# apu_mega_shield.net
KiCad netlist of a schematic drawn in EAGLE
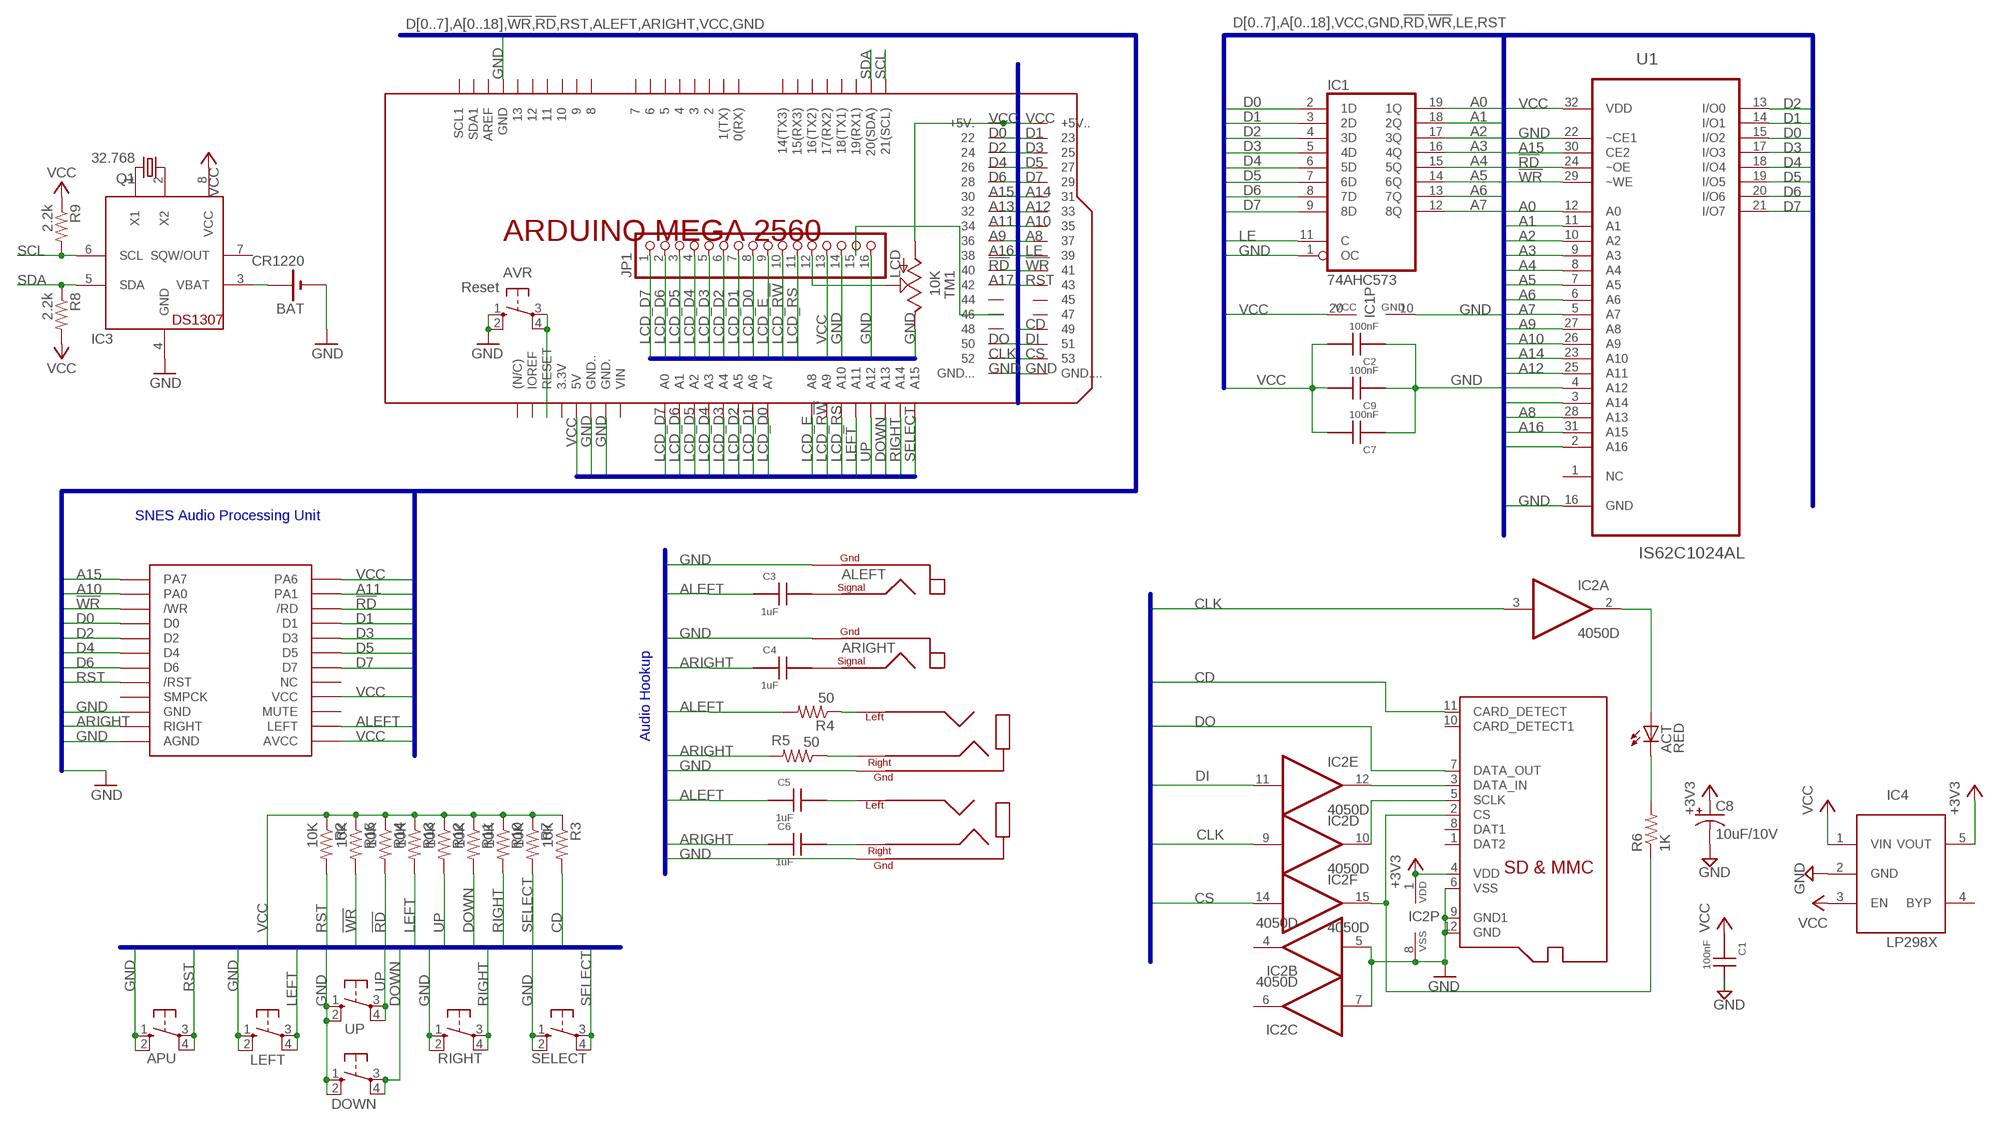
[diagram p0: schematic, sheet 1]

(export (version "E")
  (design (tool "Eeschema 10.0.6"))
  (components
    (comp (ref "ACT")
      (value "RED")
      (footprint "eagle-import:CHIP-LED0805")
      (libsource (lib "eagle-import") (part "LEDCHIP-LED0805"))
    )
    (comp (ref "APU")
      (value "Reset")
      (footprint "eagle-import:B3F-10XX")
      (libsource (lib "eagle-import") (part "10-XX"))
    )
    (comp (ref "AVR")
      (value "Reset")
      (footprint "eagle-import:B3F-10XX")
      (libsource (lib "eagle-import") (part "10-XX"))
    )
    (comp (ref "BAT")
      (value "CR1220")
      (footprint "eagle-import:CR1220-SMD")
      (libsource (lib "eagle-import") (part "CR1220SMT"))
    )
    (comp (ref "C1")
      (value "100nF")
      (footprint "eagle-import:C0805")
      (libsource (lib "eagle-import") (part "C0805"))
    )
    (comp (ref "C2")
      (value "100nF")
      (footprint "eagle-import:C0805")
      (libsource (lib "eagle-import") (part "C0805"))
    )
    (comp (ref "C3")
      (value "1uF")
      (footprint "eagle-import:C0805")
      (libsource (lib "eagle-import") (part "C0805"))
    )
    (comp (ref "C4")
      (value "1uF")
      (footprint "eagle-import:C0805")
      (libsource (lib "eagle-import") (part "C0805"))
    )
    (comp (ref "C5")
      (value "1uF")
      (footprint "eagle-import:C0805")
      (libsource (lib "eagle-import") (part "C0805"))
    )
    (comp (ref "C6")
      (value "1uF")
      (footprint "eagle-import:C0805")
      (libsource (lib "eagle-import") (part "C0805"))
    )
    (comp (ref "C7")
      (value "100nF")
      (footprint "eagle-import:C0805")
      (libsource (lib "eagle-import") (part "C0805"))
    )
    (comp (ref "C8")
      (value "10uF/10V")
      (footprint "eagle-import:A_3216-18R")
      (libsource (lib "eagle-import") (part "CPOL-USA/3216-18R"))
    )
    (comp (ref "C9")
      (value "100nF")
      (footprint "eagle-import:C0805")
      (libsource (lib "eagle-import") (part "C0805"))
    )
    (comp (ref "DOWN")
      (value "10-XX")
      (footprint "eagle-import:B3F-10XX")
      (libsource (lib "eagle-import") (part "10-XX"))
    )
    (comp (ref "IC1")
      (value "74AHC573")
      (footprint "eagle-import:SO20W")
      (libsource (lib "eagle-import") (part "74573DHCT"))
    )
    (comp (ref "IC2")
      (value "4050D")
      (footprint "eagle-import:SO16")
      (libsource (lib "eagle-import") (part "4050D"))
    )
    (comp (ref "IC3")
      (value "DS1307")
      (footprint "eagle-import:SO-08")
      (libsource (lib "eagle-import") (part "DS1307SMT"))
    )
    (comp (ref "IC4")
      (value "LP298XS")
      (footprint "eagle-import:SOT23-5L")
      (libsource (lib "eagle-import") (part "LP298XS"))
    )
    (comp (ref "JP1")
      (value "LCD")
      (footprint "eagle-import:1X16")
      (libsource (lib "eagle-import") (part "PINHD-1X16"))
    )
    (comp (ref "LEFT")
      (value "10-XX")
      (footprint "eagle-import:B3F-10XX")
      (libsource (lib "eagle-import") (part "10-XX"))
    )
    (comp (ref "Q1")
      (value "32.768")
      (footprint "eagle-import:SMD")
      (libsource (lib "eagle-import") (part "CRYTALSMD"))
    )
    (comp (ref "R2")
      (value "10K")
      (footprint "eagle-import:R0805")
      (libsource (lib "eagle-import") (part "R-US_R0805"))
    )
    (comp (ref "R3")
      (value "10K")
      (footprint "eagle-import:R0805")
      (libsource (lib "eagle-import") (part "R-US_R0805"))
    )
    (comp (ref "R4")
      (value "50")
      (footprint "eagle-import:R0805")
      (libsource (lib "eagle-import") (part "R-US_R0805"))
    )
    (comp (ref "R5")
      (value "50")
      (footprint "eagle-import:R0805")
      (libsource (lib "eagle-import") (part "R-US_R0805"))
    )
    (comp (ref "R6")
      (value "1K")
      (footprint "eagle-import:R0805")
      (libsource (lib "eagle-import") (part "R-US_R0805"))
    )
    (comp (ref "R7")
      (value "10K")
      (footprint "eagle-import:R0805")
      (libsource (lib "eagle-import") (part "R-US_R0805"))
    )
    (comp (ref "R8")
      (value "2.2k")
      (footprint "eagle-import:R0805")
      (libsource (lib "eagle-import") (part "R-US_R0805"))
    )
    (comp (ref "R9")
      (value "2.2k")
      (footprint "eagle-import:R0805")
      (libsource (lib "eagle-import") (part "R-US_R0805"))
    )
    (comp (ref "R10")
      (value "10K")
      (footprint "eagle-import:R0805")
      (libsource (lib "eagle-import") (part "R-US_R0805"))
    )
    (comp (ref "R11")
      (value "10K")
      (footprint "eagle-import:R0805")
      (libsource (lib "eagle-import") (part "R-US_R0805"))
    )
    (comp (ref "R12")
      (value "10K")
      (footprint "eagle-import:R0805")
      (libsource (lib "eagle-import") (part "R-US_R0805"))
    )
    (comp (ref "R13")
      (value "10K")
      (footprint "eagle-import:R0805")
      (libsource (lib "eagle-import") (part "R-US_R0805"))
    )
    (comp (ref "R14")
      (value "10K")
      (footprint "eagle-import:R0805")
      (libsource (lib "eagle-import") (part "R-US_R0805"))
    )
    (comp (ref "R15")
      (value "10K")
      (footprint "eagle-import:R0805")
      (libsource (lib "eagle-import") (part "R-US_R0805"))
    )
    (comp (ref "RIGHT")
      (value "10-XX")
      (footprint "eagle-import:B3F-10XX")
      (libsource (lib "eagle-import") (part "10-XX"))
    )
    (comp (ref "SELECT")
      (value "10-XX")
      (footprint "eagle-import:B3F-10XX")
      (libsource (lib "eagle-import") (part "10-XX"))
    )
    (comp (ref "TM1")
      (value "10K")
      (footprint "eagle-import:CA6H")
      (libsource (lib "eagle-import") (part "TRIM_US-CA6H"))
    )
    (comp (ref "U$1")
      (value "APU")
      (footprint "eagle-import:APU")
      (libsource (lib "eagle-import") (part "APU"))
    )
    (comp (ref "U$2")
      (value "HEADPHONE")
      (footprint "eagle-import:SJ1-3533N")
      (libsource (lib "eagle-import") (part "HEADPHONE"))
    )
    (comp (ref "U$3")
      (value "HEADPHONE")
      (footprint "eagle-import:SJ1-3533N")
      (libsource (lib "eagle-import") (part "HEADPHONE"))
    )
    (comp (ref "U$4")
      (value "RCA")
      (footprint "eagle-import:RCJ-01X")
      (libsource (lib "eagle-import") (part "RCA"))
    )
    (comp (ref "U$5")
      (value "RCA")
      (footprint "eagle-import:RCJ-01X")
      (libsource (lib "eagle-import") (part "RCA"))
    )
    (comp (ref "U$6")
      (value "ARDUINO_MEGA_2560_LITENO_LABELS")
      (footprint "eagle-import:ARDUINO_MEGA2560_LITE_NO_LABELS")
      (libsource (lib "eagle-import") (part "ARDUINO_MEGA_2560_LITENO_LABELS"))
    )
    (comp (ref "U1")
      (value "IS62C1024AL")
      (footprint "eagle-import:SOIC127P1412X305-32N")
      (fields (field (name "MPN") "IS62C1024AL-35QLI"))
      (libsource (lib "eagle-import") (part "IS62C1024AL-35QLI"))
    )
    (comp (ref "UP")
      (value "10-XX")
      (footprint "eagle-import:B3F-10XX")
      (libsource (lib "eagle-import") (part "10-XX"))
    )
    (comp (ref "X1")
      (value "MICROSDMOLEX")
      (footprint "eagle-import:MICROSD-1")
      (libsource (lib "eagle-import") (part "MICROSDMOLEX"))
    )
  )
  (nets
    (net (code "1") (name "+3V3") (class "Default")
      (node (ref "C8") (pin "+") (pinfunction "+_+") (pintype "passive"))
      (node (ref "IC2") (pin "1") (pinfunction "VDD_1") (pintype "power_in"))
      (node (ref "IC4") (pin "5") (pinfunction "VOUT_5") (pintype "bidirectional"))
      (node (ref "X1") (pin "4") (pinfunction "VDD_4") (pintype "power_in"))
    )
    (net (code "2") (name "/A0") (class "Default")
      (node (ref "IC1") (pin "19") (pinfunction "1Q_19") (pintype "tri_state"))
      (node (ref "U1") (pin "12") (pinfunction "A0_12") (pintype "input"))
    )
    (net (code "3") (name "/A1") (class "Default")
      (node (ref "IC1") (pin "18") (pinfunction "2Q_18") (pintype "tri_state"))
      (node (ref "U1") (pin "11") (pinfunction "A1_11") (pintype "input"))
    )
    (net (code "4") (name "/A2") (class "Default")
      (node (ref "IC1") (pin "17") (pinfunction "3Q_17") (pintype "tri_state"))
      (node (ref "U1") (pin "10") (pinfunction "A2_10") (pintype "input"))
    )
    (net (code "5") (name "/A3") (class "Default")
      (node (ref "IC1") (pin "16") (pinfunction "4Q_16") (pintype "tri_state"))
      (node (ref "U1") (pin "9") (pinfunction "A3_9") (pintype "input"))
    )
    (net (code "6") (name "/A4") (class "Default")
      (node (ref "IC1") (pin "15") (pinfunction "5Q_15") (pintype "tri_state"))
      (node (ref "U1") (pin "8") (pinfunction "A4_8") (pintype "input"))
    )
    (net (code "7") (name "/A5") (class "Default")
      (node (ref "IC1") (pin "14") (pinfunction "6Q_14") (pintype "tri_state"))
      (node (ref "U1") (pin "7") (pinfunction "A5_7") (pintype "input"))
    )
    (net (code "8") (name "/A6") (class "Default")
      (node (ref "IC1") (pin "13") (pinfunction "7Q_13") (pintype "tri_state"))
      (node (ref "U1") (pin "6") (pinfunction "A6_6") (pintype "input"))
    )
    (net (code "9") (name "/A7") (class "Default")
      (node (ref "IC1") (pin "12") (pinfunction "8Q_12") (pintype "tri_state"))
      (node (ref "U1") (pin "5") (pinfunction "A7_5") (pintype "input"))
    )
    (net (code "10") (name "/A8") (class "Default")
      (node (ref "U$6") (pin "37") (pinfunction "37_37") (pintype "bidirectional"))
      (node (ref "U1") (pin "28") (pinfunction "A13_28") (pintype "input"))
    )
    (net (code "11") (name "/A9") (class "Default")
      (node (ref "U$6") (pin "36") (pinfunction "36_36") (pintype "bidirectional"))
      (node (ref "U1") (pin "27") (pinfunction "A8_27") (pintype "input"))
    )
    (net (code "12") (name "/A10") (class "Default")
      (node (ref "U$1") (pin "P$3") (pinfunction "PA0_P$3") (pintype "bidirectional"))
      (node (ref "U$6") (pin "35") (pinfunction "35_35") (pintype "bidirectional"))
      (node (ref "U1") (pin "26") (pinfunction "A9_26") (pintype "input"))
    )
    (net (code "13") (name "/A11") (class "Default")
      (node (ref "U$1") (pin "P$4") (pinfunction "PA1_P$4") (pintype "bidirectional"))
      (node (ref "U$6") (pin "34") (pinfunction "34_34") (pintype "bidirectional"))
      (node (ref "U1") (pin "3") (pinfunction "A14_3") (pintype "input"))
    )
    (net (code "14") (name "/A12") (class "Default")
      (node (ref "U$6") (pin "33") (pinfunction "33_33") (pintype "bidirectional"))
      (node (ref "U1") (pin "25") (pinfunction "A11_25") (pintype "input"))
    )
    (net (code "15") (name "/A13") (class "Default")
      (node (ref "U$6") (pin "32") (pinfunction "32_32") (pintype "bidirectional"))
      (node (ref "U1") (pin "4") (pinfunction "A12_4") (pintype "input"))
    )
    (net (code "16") (name "/A14") (class "Default")
      (node (ref "U$6") (pin "31") (pinfunction "31_31") (pintype "bidirectional"))
      (node (ref "U1") (pin "23") (pinfunction "A10_23") (pintype "input"))
    )
    (net (code "17") (name "/A15") (class "Default")
      (node (ref "U$1") (pin "P$1") (pinfunction "PA7_P$1") (pintype "bidirectional"))
      (node (ref "U$6") (pin "30") (pinfunction "30_30") (pintype "bidirectional"))
      (node (ref "U1") (pin "30") (pinfunction "CE2_30") (pintype "input"))
    )
    (net (code "18") (name "/A16") (class "Default")
      (node (ref "U$6") (pin "38") (pinfunction "38_38") (pintype "bidirectional"))
      (node (ref "U1") (pin "31") (pinfunction "A15_31") (pintype "input"))
    )
    (net (code "19") (name "/A17") (class "Default")
      (node (ref "U$6") (pin "42") (pinfunction "42_42") (pintype "bidirectional"))
      (node (ref "U1") (pin "2") (pinfunction "A16_2") (pintype "input"))
    )
    (net (code "20") (name "/ALEFT") (class "Default")
      (node (ref "C3") (pin "1") (pinfunction "1_1") (pintype "bidirectional"))
      (node (ref "C5") (pin "1") (pinfunction "1_1") (pintype "bidirectional"))
      (node (ref "R4") (pin "2") (pinfunction "2_2") (pintype "passive"))
      (node (ref "U$1") (pin "P$22") (pinfunction "LEFT_P$22") (pintype "bidirectional"))
    )
    (net (code "21") (name "/ARIGHT") (class "Default")
      (node (ref "C4") (pin "1") (pinfunction "1_1") (pintype "bidirectional"))
      (node (ref "C6") (pin "1") (pinfunction "1_1") (pintype "bidirectional"))
      (node (ref "R5") (pin "2") (pinfunction "2_2") (pintype "passive"))
      (node (ref "U$1") (pin "P$21") (pinfunction "RIGHT_P$21") (pintype "bidirectional"))
    )
    (net (code "22") (name "/CD") (class "Default")
      (node (ref "R3") (pin "2") (pinfunction "2_2") (pintype "passive"))
      (node (ref "U$6") (pin "49") (pinfunction "49_49") (pintype "bidirectional"))
      (node (ref "X1") (pin "11") (pinfunction "CARD_DETECT_11") (pintype "passive"))
    )
    (net (code "23") (name "/CLK") (class "Default")
      (node (ref "IC2") (pin "3") (pinfunction "I_3") (pintype "input"))
      (node (ref "IC2") (pin "9") (pinfunction "I_9") (pintype "input"))
      (node (ref "U$6") (pin "52") (pinfunction "52_52") (pintype "bidirectional"))
    )
    (net (code "24") (name "/CS") (class "Default")
      (node (ref "IC2") (pin "14") (pinfunction "I_14") (pintype "input"))
      (node (ref "U$6") (pin "53") (pinfunction "53_53") (pintype "bidirectional"))
    )
    (net (code "25") (name "/D0") (class "Default")
      (node (ref "IC1") (pin "2") (pinfunction "1D_2") (pintype "input"))
      (node (ref "U$1") (pin "P$7") (pinfunction "D0_P$7") (pintype "bidirectional"))
      (node (ref "U$6") (pin "22") (pinfunction "22_22") (pintype "bidirectional"))
      (node (ref "U1") (pin "15") (pinfunction "I/O2_15") (pintype "bidirectional"))
    )
    (net (code "26") (name "/D1") (class "Default")
      (node (ref "IC1") (pin "3") (pinfunction "2D_3") (pintype "input"))
      (node (ref "U$1") (pin "P$8") (pinfunction "D1_P$8") (pintype "bidirectional"))
      (node (ref "U$6") (pin "23") (pinfunction "23_23") (pintype "bidirectional"))
      (node (ref "U1") (pin "14") (pinfunction "I/O1_14") (pintype "bidirectional"))
    )
    (net (code "27") (name "/D2") (class "Default")
      (node (ref "IC1") (pin "4") (pinfunction "3D_4") (pintype "input"))
      (node (ref "U$1") (pin "P$9") (pinfunction "D2_P$9") (pintype "bidirectional"))
      (node (ref "U$6") (pin "24") (pinfunction "24_24") (pintype "bidirectional"))
      (node (ref "U1") (pin "13") (pinfunction "I/O0_13") (pintype "bidirectional"))
    )
    (net (code "28") (name "/D3") (class "Default")
      (node (ref "IC1") (pin "5") (pinfunction "4D_5") (pintype "input"))
      (node (ref "U$1") (pin "P$10") (pinfunction "D3_P$10") (pintype "bidirectional"))
      (node (ref "U$6") (pin "25") (pinfunction "25_25") (pintype "bidirectional"))
      (node (ref "U1") (pin "17") (pinfunction "I/O3_17") (pintype "bidirectional"))
    )
    (net (code "29") (name "/D4") (class "Default")
      (node (ref "IC1") (pin "6") (pinfunction "5D_6") (pintype "input"))
      (node (ref "U$1") (pin "P$11") (pinfunction "D4_P$11") (pintype "bidirectional"))
      (node (ref "U$6") (pin "26") (pinfunction "26_26") (pintype "bidirectional"))
      (node (ref "U1") (pin "18") (pinfunction "I/O4_18") (pintype "bidirectional"))
    )
    (net (code "30") (name "/D5") (class "Default")
      (node (ref "IC1") (pin "7") (pinfunction "6D_7") (pintype "input"))
      (node (ref "U$1") (pin "P$12") (pinfunction "D5_P$12") (pintype "bidirectional"))
      (node (ref "U$6") (pin "27") (pinfunction "27_27") (pintype "bidirectional"))
      (node (ref "U1") (pin "19") (pinfunction "I/O5_19") (pintype "bidirectional"))
    )
    (net (code "31") (name "/D6") (class "Default")
      (node (ref "IC1") (pin "8") (pinfunction "7D_8") (pintype "input"))
      (node (ref "U$1") (pin "P$13") (pinfunction "D6_P$13") (pintype "bidirectional"))
      (node (ref "U$6") (pin "28") (pinfunction "28_28") (pintype "bidirectional"))
      (node (ref "U1") (pin "20") (pinfunction "I/O6_20") (pintype "bidirectional"))
    )
    (net (code "32") (name "/D7") (class "Default")
      (node (ref "IC1") (pin "9") (pinfunction "8D_9") (pintype "input"))
      (node (ref "U$1") (pin "P$14") (pinfunction "D7_P$14") (pintype "bidirectional"))
      (node (ref "U$6") (pin "29") (pinfunction "29_29") (pintype "bidirectional"))
      (node (ref "U1") (pin "21") (pinfunction "I/O7_21") (pintype "bidirectional"))
    )
    (net (code "33") (name "/DI") (class "Default")
      (node (ref "IC2") (pin "11") (pinfunction "I_11") (pintype "input"))
      (node (ref "U$6") (pin "51") (pinfunction "51_51") (pintype "bidirectional"))
    )
    (net (code "34") (name "/DO") (class "Default")
      (node (ref "U$6") (pin "50") (pinfunction "50_50") (pintype "bidirectional"))
      (node (ref "X1") (pin "7") (pinfunction "DATA_OUT_7") (pintype "output"))
    )
    (net (code "35") (name "/DOWN") (class "Default")
      (node (ref "DOWN") (pin "3") (pinfunction "P_3") (pintype "passive"))
      (node (ref "DOWN") (pin "4") (pinfunction "P1_4") (pintype "passive"))
      (node (ref "R11") (pin "2") (pinfunction "2_2") (pintype "passive"))
      (node (ref "U$6") (pin "A13") (pinfunction "A13_A13") (pintype "bidirectional"))
    )
    (net (code "36") (name "/LCD_D0") (class "Default")
      (node (ref "JP1") (pin "8") (pinfunction "8_8") (pintype "passive"))
      (node (ref "U$6") (pin "A7") (pinfunction "A7_A7") (pintype "bidirectional"))
    )
    (net (code "37") (name "/LCD_D1") (class "Default")
      (node (ref "JP1") (pin "7") (pinfunction "7_7") (pintype "passive"))
      (node (ref "U$6") (pin "A6") (pinfunction "A6_A6") (pintype "bidirectional"))
    )
    (net (code "38") (name "/LCD_D2") (class "Default")
      (node (ref "JP1") (pin "6") (pinfunction "6_6") (pintype "passive"))
      (node (ref "U$6") (pin "A5") (pinfunction "A5_A5") (pintype "bidirectional"))
    )
    (net (code "39") (name "/LCD_D3") (class "Default")
      (node (ref "JP1") (pin "5") (pinfunction "5_5") (pintype "passive"))
      (node (ref "U$6") (pin "A4") (pinfunction "A4_A4") (pintype "bidirectional"))
    )
    (net (code "40") (name "/LCD_D4") (class "Default")
      (node (ref "JP1") (pin "4") (pinfunction "4_4") (pintype "passive"))
      (node (ref "U$6") (pin "A3") (pinfunction "A3_A3") (pintype "bidirectional"))
    )
    (net (code "41") (name "/LCD_D5") (class "Default")
      (node (ref "JP1") (pin "3") (pinfunction "3_3") (pintype "passive"))
      (node (ref "U$6") (pin "A2") (pinfunction "A2_A2") (pintype "bidirectional"))
    )
    (net (code "42") (name "/LCD_D6") (class "Default")
      (node (ref "JP1") (pin "2") (pinfunction "2_2") (pintype "passive"))
      (node (ref "U$6") (pin "A1") (pinfunction "A1_A1") (pintype "bidirectional"))
    )
    (net (code "43") (name "/LCD_D7") (class "Default")
      (node (ref "JP1") (pin "1") (pinfunction "1_1") (pintype "passive"))
      (node (ref "U$6") (pin "A0") (pinfunction "A0_A0") (pintype "bidirectional"))
    )
    (net (code "44") (name "/LCD_E") (class "Default")
      (node (ref "JP1") (pin "9") (pinfunction "9_9") (pintype "passive"))
      (node (ref "U$6") (pin "A8") (pinfunction "A8_A8") (pintype "bidirectional"))
    )
    (net (code "45") (name "/LCD_RS") (class "Default")
      (node (ref "JP1") (pin "11") (pinfunction "11_11") (pintype "passive"))
      (node (ref "U$6") (pin "A10") (pinfunction "A10_A10") (pintype "bidirectional"))
    )
    (net (code "46") (name "/LCD_R~{W}") (class "Default")
      (node (ref "JP1") (pin "10") (pinfunction "10_10") (pintype "passive"))
      (node (ref "U$6") (pin "A9") (pinfunction "A9_A9") (pintype "bidirectional"))
    )
    (net (code "47") (name "/LE") (class "Default")
      (node (ref "IC1") (pin "11") (pinfunction "C_11") (pintype "input"))
      (node (ref "U$6") (pin "39") (pinfunction "39_39") (pintype "bidirectional"))
    )
    (net (code "48") (name "/LEFT") (class "Default")
      (node (ref "LEFT") (pin "3") (pinfunction "P_3") (pintype "passive"))
      (node (ref "LEFT") (pin "4") (pinfunction "P1_4") (pintype "passive"))
      (node (ref "R13") (pin "2") (pinfunction "2_2") (pintype "passive"))
      (node (ref "U$6") (pin "A11") (pinfunction "A11_A11") (pintype "bidirectional"))
    )
    (net (code "49") (name "/RIGHT") (class "Default")
      (node (ref "R10") (pin "2") (pinfunction "2_2") (pintype "passive"))
      (node (ref "RIGHT") (pin "3") (pinfunction "P_3") (pintype "passive"))
      (node (ref "RIGHT") (pin "4") (pinfunction "P1_4") (pintype "passive"))
      (node (ref "U$6") (pin "A14") (pinfunction "A14_A14") (pintype "bidirectional"))
    )
    (net (code "50") (name "/RST") (class "Default")
      (node (ref "APU") (pin "3") (pinfunction "P_3") (pintype "passive"))
      (node (ref "APU") (pin "4") (pinfunction "P1_4") (pintype "passive"))
      (node (ref "R2") (pin "2") (pinfunction "2_2") (pintype "passive"))
      (node (ref "U$1") (pin "P$15") (pinfunction "/RST_P$15") (pintype "bidirectional"))
      (node (ref "U$6") (pin "43") (pinfunction "43_43") (pintype "bidirectional"))
    )
    (net (code "51") (name "/SCL") (class "Default")
      (node (ref "IC3") (pin "6") (pinfunction "SCL_6") (pintype "bidirectional"))
      (node (ref "R9") (pin "2") (pinfunction "2_2") (pintype "passive"))
      (node (ref "U$6") (pin "21") (pinfunction "21(SCL)_21") (pintype "bidirectional"))
    )
    (net (code "52") (name "/SDA") (class "Default")
      (node (ref "IC3") (pin "5") (pinfunction "SDA_5") (pintype "bidirectional"))
      (node (ref "R8") (pin "1") (pinfunction "1_1") (pintype "passive"))
      (node (ref "U$6") (pin "20") (pinfunction "20(SDA)_20") (pintype "bidirectional"))
    )
    (net (code "53") (name "/SELECT") (class "Default")
      (node (ref "R7") (pin "2") (pinfunction "2_2") (pintype "passive"))
      (node (ref "SELECT") (pin "3") (pinfunction "P_3") (pintype "passive"))
      (node (ref "SELECT") (pin "4") (pinfunction "P1_4") (pintype "passive"))
      (node (ref "U$6") (pin "A15") (pinfunction "A15_A15") (pintype "bidirectional"))
    )
    (net (code "54") (name "/UP") (class "Default")
      (node (ref "R12") (pin "2") (pinfunction "2_2") (pintype "passive"))
      (node (ref "U$6") (pin "A12") (pinfunction "A12_A12") (pintype "bidirectional"))
      (node (ref "UP") (pin "3") (pinfunction "P_3") (pintype "passive"))
      (node (ref "UP") (pin "4") (pinfunction "P1_4") (pintype "passive"))
    )
    (net (code "57") (name "/~{RD}") (class "Default")
      (node (ref "R14") (pin "2") (pinfunction "2_2") (pintype "passive"))
      (node (ref "U$1") (pin "P$6") (pinfunction "/RD_P$6") (pintype "bidirectional"))
      (node (ref "U$6") (pin "40") (pinfunction "40_40") (pintype "bidirectional"))
      (node (ref "U1") (pin "24") (pinfunction "~{OE}_24") (pintype "input"))
    )
    (net (code "58") (name "/~{WR}") (class "Default")
      (node (ref "R15") (pin "2") (pinfunction "2_2") (pintype "passive"))
      (node (ref "U$1") (pin "P$5") (pinfunction "/WR_P$5") (pintype "bidirectional"))
      (node (ref "U$6") (pin "41") (pinfunction "41_41") (pintype "bidirectional"))
      (node (ref "U1") (pin "29") (pinfunction "~{WE}_29") (pintype "input"))
    )
    (net (code "59") (name "GND") (class "Default")
      (node (ref "APU") (pin "1") (pinfunction "S_1") (pintype "passive"))
      (node (ref "APU") (pin "2") (pinfunction "S1_2") (pintype "passive"))
      (node (ref "AVR") (pin "1") (pinfunction "S_1") (pintype "passive"))
      (node (ref "AVR") (pin "2") (pinfunction "S1_2") (pintype "passive"))
      (node (ref "BAT") (pin "-") (pinfunction "-_-") (pintype "passive"))
      (node (ref "C1") (pin "2") (pinfunction "2_2") (pintype "bidirectional"))
      (node (ref "C2") (pin "1") (pinfunction "1_1") (pintype "bidirectional"))
      (node (ref "C7") (pin "1") (pinfunction "1_1") (pintype "bidirectional"))
      (node (ref "C8") (pin "-") (pinfunction "-_-") (pintype "passive"))
      (node (ref "C9") (pin "1") (pinfunction "1_1") (pintype "bidirectional"))
      (node (ref "DOWN") (pin "1") (pinfunction "S_1") (pintype "passive"))
      (node (ref "DOWN") (pin "2") (pinfunction "S1_2") (pintype "passive"))
      (node (ref "IC1") (pin "1") (pinfunction "OC_1") (pintype "input"))
      (node (ref "IC1") (pin "10") (pinfunction "GND_10") (pintype "power_in"))
      (node (ref "IC2") (pin "5") (pinfunction "I_5") (pintype "input"))
      (node (ref "IC2") (pin "7") (pinfunction "I_7") (pintype "input"))
      (node (ref "IC2") (pin "8") (pinfunction "VSS_8") (pintype "power_in"))
      (node (ref "IC3") (pin "4") (pinfunction "GND_4") (pintype "power_in"))
      (node (ref "IC4") (pin "2") (pinfunction "GND_2") (pintype "bidirectional"))
      (node (ref "JP1") (pin "14") (pinfunction "14_14") (pintype "passive"))
      (node (ref "JP1") (pin "16") (pinfunction "16_16") (pintype "passive"))
      (node (ref "LEFT") (pin "1") (pinfunction "S_1") (pintype "passive"))
      (node (ref "LEFT") (pin "2") (pinfunction "S1_2") (pintype "passive"))
      (node (ref "RIGHT") (pin "1") (pinfunction "S_1") (pintype "passive"))
      (node (ref "RIGHT") (pin "2") (pinfunction "S1_2") (pintype "passive"))
      (node (ref "SELECT") (pin "1") (pinfunction "S_1") (pintype "passive"))
      (node (ref "SELECT") (pin "2") (pinfunction "S1_2") (pintype "passive"))
      (node (ref "TM1") (pin "E") (pinfunction "E_E") (pintype "passive"))
      (node (ref "U$1") (pin "P$19") (pinfunction "GND_P$19") (pintype "bidirectional"))
      (node (ref "U$1") (pin "P$23") (pinfunction "AGND_P$23") (pintype "bidirectional"))
      (node (ref "U$2") (pin "GND") (pinfunction "GND_GND") (pintype "bidirectional"))
      (node (ref "U$3") (pin "GND") (pinfunction "GND_GND") (pintype "bidirectional"))
      (node (ref "U$4") (pin "PGND1") (pinfunction "PGND1_PGND1") (pintype "bidirectional"))
      (node (ref "U$4") (pin "PGND2") (pinfunction "PGND1_PGND2") (pintype "bidirectional"))
      (node (ref "U$4") (pin "PGND3") (pinfunction "PGND1_PGND3") (pintype "bidirectional"))
      (node (ref "U$5") (pin "PGND1") (pinfunction "PGND1_PGND1") (pintype "bidirectional"))
      (node (ref "U$5") (pin "PGND2") (pinfunction "PGND1_PGND2") (pintype "bidirectional"))
      (node (ref "U$5") (pin "PGND3") (pinfunction "PGND1_PGND3") (pintype "bidirectional"))
      (node (ref "U$6") (pin "GND") (pinfunction "GND_GND") (pintype "bidirectional"))
      (node (ref "U$6") (pin "GND.") (pinfunction "GND._GND.") (pintype "bidirectional"))
      (node (ref "U$6") (pin "GND..") (pinfunction "GND.._GND..") (pintype "bidirectional"))
      (node (ref "U$6") (pin "GND...") (pinfunction "GND..._GND...") (pintype "bidirectional"))
      (node (ref "U$6") (pin "GND....") (pinfunction "GND...._GND....") (pintype "bidirectional"))
      (node (ref "U1") (pin "16") (pinfunction "GND_16") (pintype "passive"))
      (node (ref "U1") (pin "22") (pinfunction "~{CE1}_22") (pintype "input"))
      (node (ref "UP") (pin "1") (pinfunction "S_1") (pintype "passive"))
      (node (ref "UP") (pin "2") (pinfunction "S1_2") (pintype "passive"))
      (node (ref "X1") (pin "12") (pinfunction "GND_12") (pintype "power_in"))
      (node (ref "X1") (pin "6") (pinfunction "VSS_6") (pintype "power_in"))
      (node (ref "X1") (pin "9") (pinfunction "GND1_9") (pintype "power_in"))
    )
    (net (code "60") (name "Net-(ACT-PadC)") (class "Default")
      (node (ref "ACT") (pin "C") (pinfunction "C_C") (pintype "passive"))
      (node (ref "R6") (pin "2") (pinfunction "2_2") (pintype "passive"))
    )
    (net (code "61") (name "Net-(AVR-P)") (class "Default")
      (node (ref "AVR") (pin "3") (pinfunction "P_3") (pintype "passive"))
      (node (ref "AVR") (pin "4") (pinfunction "P1_4") (pintype "passive"))
      (node (ref "U$6") (pin "RESET") (pinfunction "RESET_RESET") (pintype "bidirectional"))
    )
    (net (code "62") (name "Net-(C3-Pad2)") (class "Default")
      (node (ref "C3") (pin "2") (pinfunction "2_2") (pintype "bidirectional"))
      (node (ref "U$4") (pin "PSIG") (pinfunction "PSIG_PSIG") (pintype "bidirectional"))
    )
    (net (code "63") (name "Net-(C4-Pad2)") (class "Default")
      (node (ref "C4") (pin "2") (pinfunction "2_2") (pintype "bidirectional"))
      (node (ref "U$5") (pin "PSIG") (pinfunction "PSIG_PSIG") (pintype "bidirectional"))
    )
    (net (code "64") (name "Net-(C5-Pad2)") (class "Default")
      (node (ref "C5") (pin "2") (pinfunction "2_2") (pintype "bidirectional"))
      (node (ref "U$3") (pin "LEFT") (pinfunction "LEFT_LEFT") (pintype "bidirectional"))
    )
    (net (code "65") (name "Net-(C6-Pad2)") (class "Default")
      (node (ref "C6") (pin "2") (pinfunction "2_2") (pintype "bidirectional"))
      (node (ref "U$3") (pin "RIGHT") (pinfunction "RIGHT_RIGHT") (pintype "bidirectional"))
    )
    (net (code "66") (name "Net-(IC2A-O)") (class "Default")
      (node (ref "ACT") (pin "A") (pinfunction "A_A") (pintype "passive"))
      (node (ref "IC2") (pin "2") (pinfunction "O_2") (pintype "output"))
    )
    (net (code "67") (name "Net-(IC2D-O)") (class "Default")
      (node (ref "IC2") (pin "10") (pinfunction "O_10") (pintype "output"))
      (node (ref "X1") (pin "5") (pinfunction "SCLK_5") (pintype "input"))
    )
    (net (code "68") (name "Net-(IC2E-O)") (class "Default")
      (node (ref "IC2") (pin "12") (pinfunction "O_12") (pintype "output"))
      (node (ref "X1") (pin "3") (pinfunction "DATA_IN_3") (pintype "input"))
    )
    (net (code "69") (name "Net-(IC2F-O)") (class "Default")
      (node (ref "IC2") (pin "15") (pinfunction "O_15") (pintype "output"))
      (node (ref "R6") (pin "1") (pinfunction "1_1") (pintype "passive"))
      (node (ref "X1") (pin "2") (pinfunction "CS_2") (pintype "input"))
    )
    (net (code "70") (name "Net-(IC3-VBAT)") (class "Default")
      (node (ref "BAT") (pin "+$1") (pinfunction "+_+$1") (pintype "passive"))
      (node (ref "BAT") (pin "+$2") (pinfunction "+_+$2") (pintype "passive"))
      (node (ref "IC3") (pin "3") (pinfunction "VBAT_3") (pintype "power_in"))
    )
    (net (code "71") (name "Net-(IC3-X1)") (class "Default")
      (node (ref "IC3") (pin "1") (pinfunction "X1_1") (pintype "passive"))
      (node (ref "Q1") (pin "2") (pinfunction "2_2") (pintype "passive"))
    )
    (net (code "72") (name "Net-(IC3-X2)") (class "Default")
      (node (ref "IC3") (pin "2") (pinfunction "X2_2") (pintype "passive"))
      (node (ref "Q1") (pin "1") (pinfunction "1_1") (pintype "passive"))
    )
    (net (code "73") (name "Net-(JP1-Pad12)") (class "Default")
      (node (ref "JP1") (pin "12") (pinfunction "12_12") (pintype "passive"))
      (node (ref "TM1") (pin "S") (pinfunction "S_S") (pintype "passive"))
    )
    (net (code "74") (name "Net-(JP1-Pad15)") (class "Default")
      (node (ref "JP1") (pin "15") (pinfunction "15_15") (pintype "passive"))
      (node (ref "U$6") (pin "46") (pinfunction "46_46") (pintype "bidirectional"))
    )
    (net (code "75") (name "Net-(R4-Pad1)") (class "Default")
      (node (ref "R4") (pin "1") (pinfunction "1_1") (pintype "passive"))
      (node (ref "U$2") (pin "LEFT") (pinfunction "LEFT_LEFT") (pintype "bidirectional"))
    )
    (net (code "76") (name "Net-(R5-Pad1)") (class "Default")
      (node (ref "R5") (pin "1") (pinfunction "1_1") (pintype "passive"))
      (node (ref "U$2") (pin "RIGHT") (pinfunction "RIGHT_RIGHT") (pintype "bidirectional"))
    )
    (net (code "77") (name "VCC") (class "Default")
      (node (ref "C1") (pin "1") (pinfunction "1_1") (pintype "bidirectional"))
      (node (ref "C2") (pin "2") (pinfunction "2_2") (pintype "bidirectional"))
      (node (ref "C7") (pin "2") (pinfunction "2_2") (pintype "bidirectional"))
      (node (ref "C9") (pin "2") (pinfunction "2_2") (pintype "bidirectional"))
      (node (ref "IC1") (pin "20") (pinfunction "VCC_20") (pintype "power_in"))
      (node (ref "IC3") (pin "8") (pinfunction "VCC_8") (pintype "power_in"))
      (node (ref "IC4") (pin "1") (pinfunction "VIN_1") (pintype "bidirectional"))
      (node (ref "IC4") (pin "3") (pinfunction "EN_3") (pintype "bidirectional"))
      (node (ref "JP1") (pin "13") (pinfunction "13_13") (pintype "passive"))
      (node (ref "R10") (pin "1") (pinfunction "1_1") (pintype "passive"))
      (node (ref "R11") (pin "1") (pinfunction "1_1") (pintype "passive"))
      (node (ref "R12") (pin "1") (pinfunction "1_1") (pintype "passive"))
      (node (ref "R13") (pin "1") (pinfunction "1_1") (pintype "passive"))
      (node (ref "R14") (pin "1") (pinfunction "1_1") (pintype "passive"))
      (node (ref "R15") (pin "1") (pinfunction "1_1") (pintype "passive"))
      (node (ref "R2") (pin "1") (pinfunction "1_1") (pintype "passive"))
      (node (ref "R3") (pin "1") (pinfunction "1_1") (pintype "passive"))
      (node (ref "R7") (pin "1") (pinfunction "1_1") (pintype "passive"))
      (node (ref "R8") (pin "2") (pinfunction "2_2") (pintype "passive"))
      (node (ref "R9") (pin "1") (pinfunction "1_1") (pintype "passive"))
      (node (ref "TM1") (pin "A") (pinfunction "A_A") (pintype "passive"))
      (node (ref "U$1") (pin "P$18") (pinfunction "VCC_P$18") (pintype "bidirectional"))
      (node (ref "U$1") (pin "P$2") (pinfunction "PA6_P$2") (pintype "bidirectional"))
      (node (ref "U$1") (pin "P$24") (pinfunction "AVCC_P$24") (pintype "bidirectional"))
      (node (ref "U$6") (pin "5V") (pinfunction "5V_5V") (pintype "bidirectional"))
      (node (ref "U$6") (pin "5V.") (pinfunction "+5V._5V.") (pintype "bidirectional"))
      (node (ref "U$6") (pin "5V..") (pinfunction "+5V.._5V..") (pintype "bidirectional"))
      (node (ref "U1") (pin "32") (pinfunction "VDD_32") (pintype "power_in"))
    )
    (net (code "78") (name "unconnected-(IC2B-O-Pad4)") (class "Default")
      (node (ref "IC2") (pin "4") (pinfunction "O_4") (pintype "output"))
    )
    (net (code "79") (name "unconnected-(IC2C-O-Pad6)") (class "Default")
      (node (ref "IC2") (pin "6") (pinfunction "O_6") (pintype "output"))
    )
    (net (code "80") (name "unconnected-(IC3-SQW{slash}OUT-Pad7)") (class "Default")
      (node (ref "IC3") (pin "7") (pinfunction "SQW/OUT_7") (pintype "bidirectional"))
    )
    (net (code "81") (name "unconnected-(IC4-BYP-Pad4)") (class "Default")
      (node (ref "IC4") (pin "4") (pinfunction "BYP_4") (pintype "bidirectional"))
    )
    (net (code "82") (name "unconnected-(U$1-MUTE-PadP$20)") (class "Default")
      (node (ref "U$1") (pin "P$20") (pinfunction "MUTE_P$20") (pintype "bidirectional"))
    )
    (net (code "83") (name "unconnected-(U$1-NC-PadP$16)") (class "Default")
      (node (ref "U$1") (pin "P$16") (pinfunction "NC_P$16") (pintype "bidirectional"))
    )
    (net (code "84") (name "unconnected-(U$1-SMPCK-PadP$17)") (class "Default")
      (node (ref "U$1") (pin "P$17") (pinfunction "SMPCK_P$17") (pintype "bidirectional"))
    )
    (net (code "85") (name "unconnected-(U$6-(N{slash}C)-PadN{slash}C)") (class "Default")
      (node (ref "U$6") (pin "N/C") (pinfunction "(N/C)_N/C") (pintype "bidirectional"))
    )
    (net (code "86") (name "unconnected-(U$6-0(RX)-Pad0)") (class "Default")
      (node (ref "U$6") (pin "0") (pinfunction "0(RX)_0") (pintype "bidirectional"))
    )
    (net (code "87") (name "unconnected-(U$6-1(TX)-Pad1)") (class "Default")
      (node (ref "U$6") (pin "1") (pinfunction "1(TX)_1") (pintype "bidirectional"))
    )
    (net (code "88") (name "unconnected-(U$6-14(TX3)-Pad14)") (class "Default")
      (node (ref "U$6") (pin "14") (pinfunction "14(TX3)_14") (pintype "bidirectional"))
    )
    (net (code "89") (name "unconnected-(U$6-15(RX3)-Pad15)") (class "Default")
      (node (ref "U$6") (pin "15") (pinfunction "15(RX3)_15") (pintype "bidirectional"))
    )
    (net (code "90") (name "unconnected-(U$6-16(TX2)-Pad16)") (class "Default")
      (node (ref "U$6") (pin "16") (pinfunction "16(TX2)_16") (pintype "bidirectional"))
    )
    (net (code "91") (name "unconnected-(U$6-17(RX2)-Pad17)") (class "Default")
      (node (ref "U$6") (pin "17") (pinfunction "17(RX2)_17") (pintype "bidirectional"))
    )
    (net (code "92") (name "unconnected-(U$6-18(TX1)-Pad18)") (class "Default")
      (node (ref "U$6") (pin "18") (pinfunction "18(TX1)_18") (pintype "bidirectional"))
    )
    (net (code "93") (name "unconnected-(U$6-19(RX1)-Pad19)") (class "Default")
      (node (ref "U$6") (pin "19") (pinfunction "19(RX1)_19") (pintype "bidirectional"))
    )
    (net (code "94") (name "unconnected-(U$6-IOREF-PadI{slash}OREF)") (class "Default")
      (node (ref "U$6") (pin "I/OREF") (pinfunction "IOREF_I/OREF") (pintype "bidirectional"))
    )
    (net (code "95") (name "unconnected-(U$6-Pad2)") (class "Default")
      (node (ref "U$6") (pin "2") (pinfunction "2_2") (pintype "bidirectional"))
    )
    (net (code "96") (name "unconnected-(U$6-Pad3)") (class "Default")
      (node (ref "U$6") (pin "3") (pinfunction "3_3") (pintype "bidirectional"))
    )
    (net (code "97") (name "unconnected-(U$6-Pad3.3V)") (class "Default")
      (node (ref "U$6") (pin "3.3V") (pinfunction "3.3V_3.3V") (pintype "bidirectional"))
    )
    (net (code "98") (name "unconnected-(U$6-Pad4)") (class "Default")
      (node (ref "U$6") (pin "4") (pinfunction "4_4") (pintype "bidirectional"))
    )
    (net (code "99") (name "unconnected-(U$6-Pad5)") (class "Default")
      (node (ref "U$6") (pin "5") (pinfunction "5_5") (pintype "bidirectional"))
    )
    (net (code "100") (name "unconnected-(U$6-Pad6)") (class "Default")
      (node (ref "U$6") (pin "6") (pinfunction "6_6") (pintype "bidirectional"))
    )
    (net (code "101") (name "unconnected-(U$6-Pad7)") (class "Default")
      (node (ref "U$6") (pin "7") (pinfunction "7_7") (pintype "bidirectional"))
    )
    (net (code "102") (name "unconnected-(U$6-Pad8)") (class "Default")
      (node (ref "U$6") (pin "8") (pinfunction "8_8") (pintype "bidirectional"))
    )
    (net (code "103") (name "unconnected-(U$6-Pad9)") (class "Default")
      (node (ref "U$6") (pin "9") (pinfunction "9_9") (pintype "bidirectional"))
    )
    (net (code "104") (name "unconnected-(U$6-Pad10)") (class "Default")
      (node (ref "U$6") (pin "10") (pinfunction "10_10") (pintype "bidirectional"))
    )
    (net (code "105") (name "unconnected-(U$6-Pad11)") (class "Default")
      (node (ref "U$6") (pin "11") (pinfunction "11_11") (pintype "bidirectional"))
    )
    (net (code "106") (name "unconnected-(U$6-Pad12)") (class "Default")
      (node (ref "U$6") (pin "12") (pinfunction "12_12") (pintype "bidirectional"))
    )
    (net (code "107") (name "unconnected-(U$6-Pad13)") (class "Default")
      (node (ref "U$6") (pin "13") (pinfunction "13_13") (pintype "bidirectional"))
    )
    (net (code "108") (name "unconnected-(U$6-Pad44)") (class "Default")
      (node (ref "U$6") (pin "44") (pinfunction "44_44") (pintype "bidirectional"))
    )
    (net (code "109") (name "unconnected-(U$6-Pad45)") (class "Default")
      (node (ref "U$6") (pin "45") (pinfunction "45_45") (pintype "bidirectional"))
    )
    (net (code "110") (name "unconnected-(U$6-Pad47)") (class "Default")
      (node (ref "U$6") (pin "47") (pinfunction "47_47") (pintype "bidirectional"))
    )
    (net (code "111") (name "unconnected-(U$6-Pad48)") (class "Default")
      (node (ref "U$6") (pin "48") (pinfunction "48_48") (pintype "bidirectional"))
    )
    (net (code "112") (name "unconnected-(U$6-PadAREF)") (class "Default")
      (node (ref "U$6") (pin "AREF") (pinfunction "AREF_AREF") (pintype "bidirectional"))
    )
    (net (code "113") (name "unconnected-(U$6-PadSCL1)") (class "Default")
      (node (ref "U$6") (pin "SCL1") (pinfunction "SCL1_SCL1") (pintype "bidirectional"))
    )
    (net (code "114") (name "unconnected-(U$6-PadSDA1)") (class "Default")
      (node (ref "U$6") (pin "SDA1") (pinfunction "SDA1_SDA1") (pintype "bidirectional"))
    )
    (net (code "115") (name "unconnected-(U$6-PadVIN)") (class "Default")
      (node (ref "U$6") (pin "VIN") (pinfunction "VIN_VIN") (pintype "bidirectional"))
    )
    (net (code "116") (name "unconnected-(U1-NC-Pad1)") (class "Default")
      (node (ref "U1") (pin "1") (pinfunction "NC_1") (pintype "no_connect"))
    )
    (net (code "117") (name "unconnected-(X1-CARD_DETECT1-Pad10)") (class "Default")
      (node (ref "X1") (pin "10") (pinfunction "CARD_DETECT1_10") (pintype "passive"))
    )
    (net (code "118") (name "unconnected-(X1-DAT1-Pad8)") (class "Default")
      (node (ref "X1") (pin "8") (pinfunction "DAT1_8") (pintype "bidirectional"))
    )
    (net (code "119") (name "unconnected-(X1-DAT2-Pad1)") (class "Default")
      (node (ref "X1") (pin "1") (pinfunction "DAT2_1") (pintype "bidirectional"))
    )
  )
)
